# Sheet2.net
KiCad netlist of a schematic drawn in Altium Designer
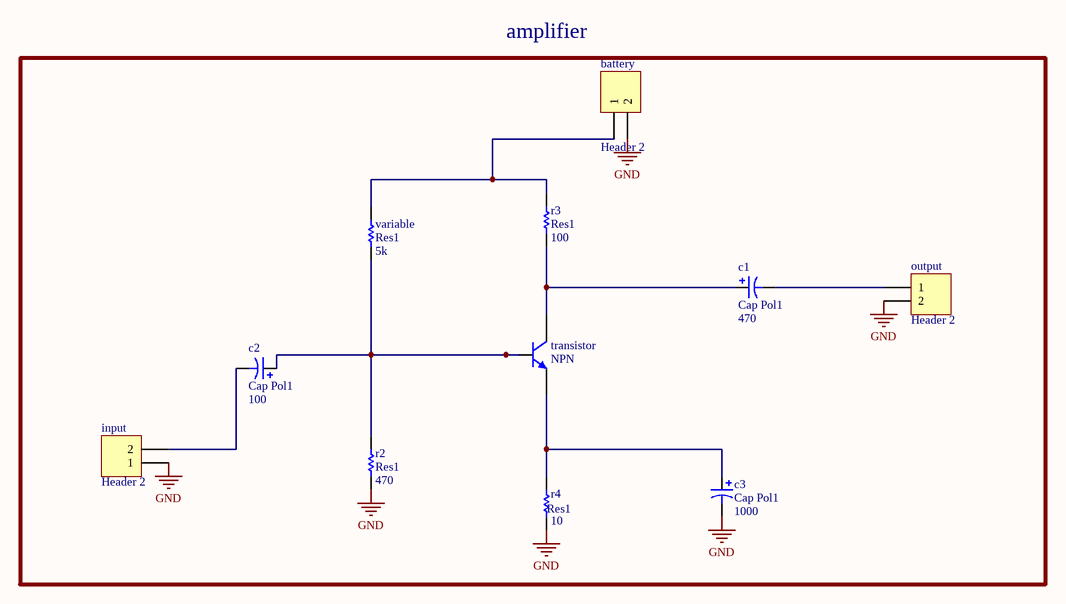
[diagram p0: Sheet2.SchDoc]

(export (version "E")
  (design (tool "Eeschema 10.0.6"))
  (components
    (comp (ref "battery")
      (value "Header 2")
      (footprint "HDR1X2")
      (description "Header, 2-Pin")
      (fields (field (name "PUBLISHER") "Altium Limited"))
      (libsource (lib "") (part "Header 2_2"))
    )
    (comp (ref "c1")
      (value "Cap Pol1")
      (footprint "RB7.6-15")
      (description "Polarized Capacitor (Radial)")
      (fields (field (name "ALTIUM_VALUE") "470") (field (name "PUBLISHER") "Altium Limited"))
      (libsource (lib "Miscellaneous Devices") (part "Cap Pol1"))
    )
    (comp (ref "c2")
      (value "Cap Pol1")
      (footprint "RB7.6-15")
      (description "Polarized Capacitor (Radial)")
      (fields (field (name "ALTIUM_VALUE") "100") (field (name "PUBLISHER") "Altium Limited"))
      (libsource (lib "Miscellaneous Devices") (part "Cap Pol1"))
    )
    (comp (ref "c3")
      (value "Cap Pol1")
      (footprint "RB7.6-15")
      (description "Polarized Capacitor (Radial)")
      (fields (field (name "ALTIUM_VALUE") "1000") (field (name "PUBLISHER") "Altium Limited"))
      (libsource (lib "Miscellaneous Devices") (part "Cap Pol1"))
    )
    (comp (ref "input")
      (value "Header 2")
      (footprint "HDR1X2")
      (description "Header, 2-Pin")
      (fields (field (name "PUBLISHER") "Altium Limited"))
      (libsource (lib "") (part "Header 2_1"))
    )
    (comp (ref "output")
      (value "Header 2")
      (footprint "HDR1X2")
      (description "Header, 2-Pin")
      (fields (field (name "PUBLISHER") "Altium Limited"))
      (libsource (lib "Miscellaneous Connectors") (part "Header 2"))
    )
    (comp (ref "r2")
      (value "Res1")
      (footprint "AXIAL-0.3")
      (description "Resistor")
      (fields (field (name "ALTIUM_VALUE") "470") (field (name "PUBLISHER") "Altium Limited"))
      (libsource (lib "Miscellaneous Devices") (part "Res1"))
    )
    (comp (ref "r3")
      (value "Res1")
      (footprint "AXIAL-0.3")
      (description "Resistor")
      (fields (field (name "ALTIUM_VALUE") "100") (field (name "PUBLISHER") "Altium Limited"))
      (libsource (lib "Miscellaneous Devices") (part "Res1"))
    )
    (comp (ref "r4")
      (value "Res1")
      (footprint "AXIAL-0.3")
      (description "Resistor")
      (fields (field (name "ALTIUM_VALUE") "10") (field (name "PUBLISHER") "Altium Limited"))
      (libsource (lib "Miscellaneous Devices") (part "Res1"))
    )
    (comp (ref "transistor")
      (value "NPN")
      (footprint "TO-226-AA")
      (description "NPN Bipolar Transistor")
      (fields (field (name "PUBLISHER") "Altium Limited"))
      (libsource (lib "Miscellaneous Devices") (part "NPN"))
    )
    (comp (ref "variable")
      (value "Res1")
      (footprint "AXIAL-0.3")
      (description "Resistor")
      (fields (field (name "ALTIUM_VALUE") "5k") (field (name "PUBLISHER") "Altium Limited"))
      (libsource (lib "Miscellaneous Devices") (part "Res1"))
    )
  )
  (nets
    (net (code "1") (name "GND") (class "Default")
      (node (ref "battery") (pin "2") (pinfunction "2_2") (pintype "passive"))
      (node (ref "c3") (pin "2") (pinfunction "2_2") (pintype "passive"))
      (node (ref "input") (pin "1") (pinfunction "1_1") (pintype "passive"))
      (node (ref "output") (pin "2") (pinfunction "2_2") (pintype "passive"))
      (node (ref "r2") (pin "2") (pinfunction "2_2") (pintype "passive"))
      (node (ref "r4") (pin "2") (pinfunction "2_2") (pintype "passive"))
    )
    (net (code "2") (name "Net-(battery-Pad1)") (class "Default")
      (node (ref "battery") (pin "1") (pinfunction "1_1") (pintype "passive"))
      (node (ref "r3") (pin "1") (pinfunction "1_1") (pintype "passive"))
      (node (ref "variable") (pin "1") (pinfunction "1_1") (pintype "passive"))
    )
    (net (code "3") (name "Net-(c1-Pad2)") (class "Default")
      (node (ref "c1") (pin "2") (pinfunction "2_2") (pintype "passive"))
      (node (ref "output") (pin "1") (pinfunction "1_1") (pintype "passive"))
    )
    (net (code "4") (name "Net-(c2-Pad2)") (class "Default")
      (node (ref "c2") (pin "2") (pinfunction "2_2") (pintype "passive"))
      (node (ref "input") (pin "2") (pinfunction "2_2") (pintype "passive"))
    )
    (net (code "5") (name "Net-(transistor-B)") (class "Default")
      (node (ref "c2") (pin "1") (pinfunction "1_1") (pintype "passive"))
      (node (ref "r2") (pin "1") (pinfunction "1_1") (pintype "passive"))
      (node (ref "transistor") (pin "2") (pinfunction "B_2") (pintype "passive"))
      (node (ref "variable") (pin "2") (pinfunction "2_2") (pintype "passive"))
    )
    (net (code "6") (name "Net-(transistor-C)") (class "Default")
      (node (ref "c1") (pin "1") (pinfunction "1_1") (pintype "passive"))
      (node (ref "r3") (pin "2") (pinfunction "2_2") (pintype "passive"))
      (node (ref "transistor") (pin "1") (pinfunction "C_1") (pintype "passive"))
    )
    (net (code "7") (name "Net-(transistor-E)") (class "Default")
      (node (ref "c3") (pin "1") (pinfunction "1_1") (pintype "passive"))
      (node (ref "r4") (pin "1") (pinfunction "1_1") (pintype "passive"))
      (node (ref "transistor") (pin "3") (pinfunction "E_3") (pintype "passive"))
    )
  )
)
